# host.net
KiCad netlist of a schematic drawn in EAGLE
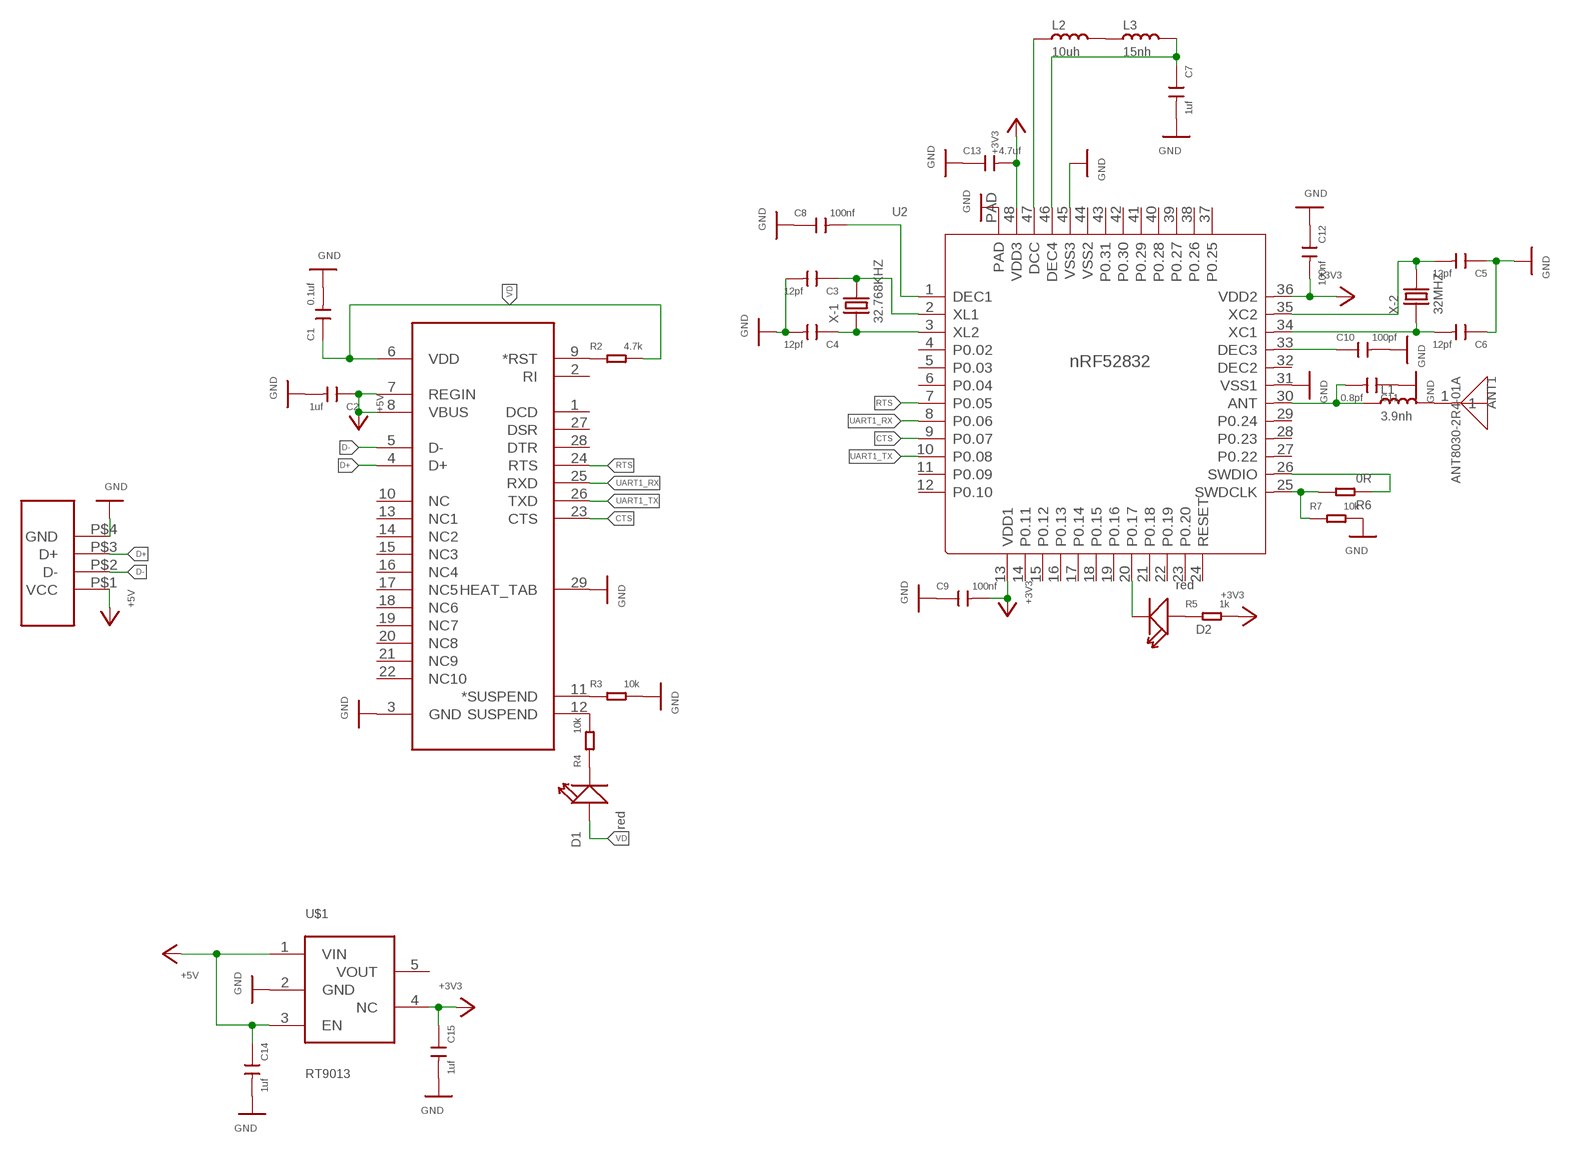
[diagram p0: schematic, sheet 1]

(export (version "E")
  (design (tool "Eeschema 10.0.6"))
  (components
    (comp (ref "ANT1")
      (value "ANT8030-2R4-01A")
      (footprint "eagle-import:ANTENNA")
      (libsource (lib "eagle-import") (part "ANTENNA"))
    )
    (comp (ref "C1")
      (value "0.1uf")
      (footprint "eagle-import:C0402")
      (fields (field (name "MPN") "CC0402BRNPO9BNR50"))
      (libsource (lib "eagle-import") (part "C(0402)"))
    )
    (comp (ref "C2")
      (value "1uf")
      (footprint "eagle-import:C0402")
      (fields (field (name "MPN") "CC0402BRNPO9BNR50"))
      (libsource (lib "eagle-import") (part "C(0402)"))
    )
    (comp (ref "C3")
      (value "12pf")
      (footprint "eagle-import:C0402")
      (fields (field (name "MPN") "CC0402BRNPO9BNR50"))
      (libsource (lib "eagle-import") (part "C(0402)"))
    )
    (comp (ref "C4")
      (value "12pf")
      (footprint "eagle-import:C0402")
      (fields (field (name "MPN") "CC0402BRNPO9BNR50"))
      (libsource (lib "eagle-import") (part "C(0402)"))
    )
    (comp (ref "C5")
      (value "12pf")
      (footprint "eagle-import:C0402")
      (fields (field (name "MPN") "CC0402BRNPO9BNR50"))
      (libsource (lib "eagle-import") (part "C(0402)"))
    )
    (comp (ref "C6")
      (value "12pf")
      (footprint "eagle-import:C0402")
      (fields (field (name "MPN") "CC0402BRNPO9BNR50"))
      (libsource (lib "eagle-import") (part "C(0402)"))
    )
    (comp (ref "C7")
      (value "1uf")
      (footprint "eagle-import:C0402")
      (fields (field (name "MPN") "CC0402BRNPO9BNR50"))
      (libsource (lib "eagle-import") (part "C(0402)"))
    )
    (comp (ref "C8")
      (value "100nf")
      (footprint "eagle-import:C0402")
      (fields (field (name "MPN") "CC0402BRNPO9BNR50"))
      (libsource (lib "eagle-import") (part "C(0402)"))
    )
    (comp (ref "C9")
      (value "100nf")
      (footprint "eagle-import:C0402")
      (fields (field (name "MPN") "CC0402BRNPO9BNR50"))
      (libsource (lib "eagle-import") (part "C(0402)"))
    )
    (comp (ref "C10")
      (value "100pf")
      (footprint "eagle-import:C0402")
      (fields (field (name "MPN") "CC0402BRNPO9BNR50"))
      (libsource (lib "eagle-import") (part "C(0402)"))
    )
    (comp (ref "C11")
      (value "0.8pf")
      (footprint "eagle-import:C0402")
      (fields (field (name "MPN") "CC0402BRNPO9BNR50"))
      (libsource (lib "eagle-import") (part "C(0402)"))
    )
    (comp (ref "C12")
      (value "100nf")
      (footprint "eagle-import:C0402")
      (fields (field (name "MPN") "CC0402BRNPO9BNR50"))
      (libsource (lib "eagle-import") (part "C(0402)"))
    )
    (comp (ref "C13")
      (value "4.7uf")
      (footprint "eagle-import:C0402")
      (fields (field (name "MPN") "CC0402BRNPO9BNR50"))
      (libsource (lib "eagle-import") (part "C(0402)"))
    )
    (comp (ref "C14")
      (value "1uf")
      (footprint "eagle-import:C0402")
      (fields (field (name "MPN") "CC0402BRNPO9BNR50"))
      (libsource (lib "eagle-import") (part "C(0402)"))
    )
    (comp (ref "C15")
      (value "1uf")
      (footprint "eagle-import:C0402")
      (fields (field (name "MPN") "CC0402BRNPO9BNR50"))
      (libsource (lib "eagle-import") (part "C(0402)"))
    )
    (comp (ref "CP1")
      (value "CP2102")
      (footprint "eagle-import:QFN28G_0.5-5X5MM")
      (libsource (lib "eagle-import") (part "CP2102"))
    )
    (comp (ref "D1")
      (value "red")
      (footprint "eagle-import:LED-0402")
      (fields (field (name "MPN") "BL-HB337A-AV-TRB"))
      (libsource (lib "eagle-import") (part "LED-(0402)"))
    )
    (comp (ref "D2")
      (value "red")
      (footprint "eagle-import:LED-0402")
      (fields (field (name "MPN") "BL-HB337A-AV-TRB"))
      (libsource (lib "eagle-import") (part "LED-(0402)"))
    )
    (comp (ref "L1")
      (value "3.9nh")
      (footprint "eagle-import:L0402")
      (libsource (lib "eagle-import") (part "INDUCTOR(0402)"))
    )
    (comp (ref "L2")
      (value "10uh")
      (footprint "eagle-import:L0402")
      (libsource (lib "eagle-import") (part "INDUCTOR(0402)"))
    )
    (comp (ref "L3")
      (value "15nh")
      (footprint "eagle-import:L0402")
      (libsource (lib "eagle-import") (part "INDUCTOR(0402)"))
    )
    (comp (ref "R2")
      (value "4.7k")
      (footprint "eagle-import:R0402")
      (fields (field (name "MPN") "RC0402JR-070RL"))
      (libsource (lib "eagle-import") (part "RES-(0402)"))
    )
    (comp (ref "R3")
      (value "10k")
      (footprint "eagle-import:R0402")
      (fields (field (name "MPN") "RC0402JR-070RL"))
      (libsource (lib "eagle-import") (part "RES-(0402)"))
    )
    (comp (ref "R4")
      (value "10k")
      (footprint "eagle-import:R0402")
      (fields (field (name "MPN") "RC0402JR-070RL"))
      (libsource (lib "eagle-import") (part "RES-(0402)"))
    )
    (comp (ref "R5")
      (value "1k")
      (footprint "eagle-import:R0402")
      (fields (field (name "MPN") "RC0402JR-070RL"))
      (libsource (lib "eagle-import") (part "RES-(0402)"))
    )
    (comp (ref "R6")
      (value "0R")
      (footprint "eagle-import:R0603")
      (fields (field (name "MPN") "RC0603FR-071M1L"))
      (libsource (lib "eagle-import") (part "RES-(0603)"))
    )
    (comp (ref "R7")
      (value "10k")
      (footprint "eagle-import:R0402")
      (fields (field (name "MPN") "RC0402JR-070RL"))
      (libsource (lib "eagle-import") (part "RES-(0402)"))
    )
    (comp (ref "U$1")
      (value "RT9013")
      (footprint "eagle-import:SC-70-5")
      (libsource (lib "eagle-import") (part "RT9013"))
    )
    (comp (ref "U1")
      (value "USB-4PIN")
      (footprint "eagle-import:USB-HW-4PIN")
      (libsource (lib "eagle-import") (part "USB-4PIN"))
    )
    (comp (ref "U2")
      (value "RF-51822")
      (footprint "eagle-import:QFN48G-0.4-6X6MM")
      (libsource (lib "eagle-import") (part "IC-NRF-52832(QFN48)"))
    )
    (comp (ref "X-1")
      (value "32.768KHZ")
      (footprint "eagle-import:32.768KHZ")
      (libsource (lib "eagle-import") (part "32.768KHZ"))
    )
    (comp (ref "X-2")
      (value "32MHZ")
      (footprint "eagle-import:16MHZ")
      (libsource (lib "eagle-import") (part "16MHZ"))
    )
  )
  (nets
    (net (code "1") (name "+3V3") (class "Default")
      (node (ref "C12") (pin "2") (pinfunction "2_2") (pintype "passive"))
      (node (ref "C13") (pin "2") (pinfunction "2_2") (pintype "passive"))
      (node (ref "C15") (pin "1") (pinfunction "1_1") (pintype "passive"))
      (node (ref "C9") (pin "2") (pinfunction "2_2") (pintype "passive"))
      (node (ref "R5") (pin "2") (pinfunction "2_2") (pintype "passive"))
      (node (ref "U$1") (pin "4") (pinfunction "NC_4") (pintype "bidirectional"))
      (node (ref "U2") (pin "13") (pinfunction "VDD1_13") (pintype "bidirectional"))
      (node (ref "U2") (pin "36") (pinfunction "VDD2_36") (pintype "bidirectional"))
      (node (ref "U2") (pin "48") (pinfunction "VDD3_48") (pintype "bidirectional"))
    )
    (net (code "2") (name "+5V") (class "Default")
      (node (ref "C14") (pin "1") (pinfunction "1_1") (pintype "passive"))
      (node (ref "C2") (pin "1") (pinfunction "1_1") (pintype "passive"))
      (node (ref "CP1") (pin "7") (pinfunction "REGIN_7") (pintype "bidirectional"))
      (node (ref "CP1") (pin "8") (pinfunction "VBUS_8") (pintype "bidirectional"))
      (node (ref "U$1") (pin "1") (pinfunction "VIN_1") (pintype "bidirectional"))
      (node (ref "U$1") (pin "3") (pinfunction "EN_3") (pintype "bidirectional"))
      (node (ref "U1") (pin "P$1") (pinfunction "VCC_P$1") (pintype "bidirectional"))
    )
    (net (code "3") (name "CTS") (class "Default")
      (node (ref "CP1") (pin "23") (pinfunction "CTS_23") (pintype "bidirectional"))
      (node (ref "U2") (pin "9") (pinfunction "P0.07_9") (pintype "bidirectional"))
    )
    (net (code "4") (name "D+") (class "Default")
      (node (ref "CP1") (pin "4") (pinfunction "D+_4") (pintype "bidirectional"))
      (node (ref "U1") (pin "P$3") (pinfunction "D+_P$3") (pintype "bidirectional"))
    )
    (net (code "5") (name "D-") (class "Default")
      (node (ref "CP1") (pin "5") (pinfunction "D-_5") (pintype "bidirectional"))
      (node (ref "U1") (pin "P$2") (pinfunction "D-_P$2") (pintype "bidirectional"))
    )
    (net (code "6") (name "GND") (class "Default")
      (node (ref "C1") (pin "2") (pinfunction "2_2") (pintype "passive"))
      (node (ref "C10") (pin "2") (pinfunction "2_2") (pintype "passive"))
      (node (ref "C11") (pin "1") (pinfunction "1_1") (pintype "passive"))
      (node (ref "C12") (pin "1") (pinfunction "1_1") (pintype "passive"))
      (node (ref "C13") (pin "1") (pinfunction "1_1") (pintype "passive"))
      (node (ref "C14") (pin "2") (pinfunction "2_2") (pintype "passive"))
      (node (ref "C15") (pin "2") (pinfunction "2_2") (pintype "passive"))
      (node (ref "C2") (pin "2") (pinfunction "2_2") (pintype "passive"))
      (node (ref "C3") (pin "2") (pinfunction "2_2") (pintype "passive"))
      (node (ref "C4") (pin "2") (pinfunction "2_2") (pintype "passive"))
      (node (ref "C5") (pin "1") (pinfunction "1_1") (pintype "passive"))
      (node (ref "C6") (pin "1") (pinfunction "1_1") (pintype "passive"))
      (node (ref "C7") (pin "2") (pinfunction "2_2") (pintype "passive"))
      (node (ref "C8") (pin "1") (pinfunction "1_1") (pintype "passive"))
      (node (ref "C9") (pin "1") (pinfunction "1_1") (pintype "passive"))
      (node (ref "CP1") (pin "29") (pinfunction "HEAT_TAB_29") (pintype "bidirectional"))
      (node (ref "CP1") (pin "3") (pinfunction "GND_3") (pintype "bidirectional"))
      (node (ref "R3") (pin "2") (pinfunction "2_2") (pintype "passive"))
      (node (ref "R7") (pin "2") (pinfunction "2_2") (pintype "passive"))
      (node (ref "U$1") (pin "2") (pinfunction "GND_2") (pintype "bidirectional"))
      (node (ref "U1") (pin "P$4") (pinfunction "GND_P$4") (pintype "bidirectional"))
      (node (ref "U2") (pin "31") (pinfunction "VSS1_31") (pintype "bidirectional"))
      (node (ref "U2") (pin "45") (pinfunction "VSS3_45") (pintype "bidirectional"))
      (node (ref "U2") (pin "PAD") (pinfunction "PAD_PAD") (pintype "bidirectional"))
    )
    (net (code "7") (name "Net-(ANT1-Pad1)") (class "Default")
      (node (ref "ANT1") (pin "1") (pinfunction "1_1") (pintype "bidirectional"))
      (node (ref "L1") (pin "2") (pinfunction "2_2") (pintype "passive"))
    )
    (net (code "8") (name "Net-(CP1-*RST)") (class "Default")
      (node (ref "CP1") (pin "9") (pinfunction "*RST_9") (pintype "bidirectional"))
      (node (ref "R2") (pin "1") (pinfunction "1_1") (pintype "passive"))
    )
    (net (code "9") (name "Net-(CP1-*SUSPEND)") (class "Default")
      (node (ref "CP1") (pin "11") (pinfunction "*SUSPEND_11") (pintype "bidirectional"))
      (node (ref "R3") (pin "1") (pinfunction "1_1") (pintype "passive"))
    )
    (net (code "10") (name "Net-(CP1-SUSPEND)") (class "Default")
      (node (ref "CP1") (pin "12") (pinfunction "SUSPEND_12") (pintype "bidirectional"))
      (node (ref "R4") (pin "2") (pinfunction "2_2") (pintype "passive"))
    )
    (net (code "11") (name "Net-(D1-Pad-)") (class "Default")
      (node (ref "D1") (pin "-") (pinfunction "-_-") (pintype "passive"))
      (node (ref "R4") (pin "1") (pinfunction "1_1") (pintype "passive"))
    )
    (net (code "12") (name "Net-(D2-Pad+)") (class "Default")
      (node (ref "D2") (pin "+") (pinfunction "+_+") (pintype "passive"))
      (node (ref "R5") (pin "1") (pinfunction "1_1") (pintype "passive"))
    )
    (net (code "13") (name "Net-(L2-Pad2)") (class "Default")
      (node (ref "L2") (pin "2") (pinfunction "2_2") (pintype "passive"))
      (node (ref "L3") (pin "1") (pinfunction "1_1") (pintype "passive"))
    )
    (net (code "14") (name "Net-(U2-ANT)") (class "Default")
      (node (ref "C11") (pin "2") (pinfunction "2_2") (pintype "passive"))
      (node (ref "L1") (pin "1") (pinfunction "1_1") (pintype "passive"))
      (node (ref "U2") (pin "30") (pinfunction "ANT_30") (pintype "bidirectional"))
    )
    (net (code "15") (name "Net-(U2-DCC)") (class "Default")
      (node (ref "L2") (pin "1") (pinfunction "1_1") (pintype "passive"))
      (node (ref "U2") (pin "47") (pinfunction "DCC_47") (pintype "bidirectional"))
    )
    (net (code "16") (name "Net-(U2-DEC1)") (class "Default")
      (node (ref "C8") (pin "2") (pinfunction "2_2") (pintype "passive"))
      (node (ref "U2") (pin "1") (pinfunction "DEC1_1") (pintype "bidirectional"))
    )
    (net (code "17") (name "Net-(U2-DEC3)") (class "Default")
      (node (ref "C10") (pin "1") (pinfunction "1_1") (pintype "passive"))
      (node (ref "U2") (pin "33") (pinfunction "DEC3_33") (pintype "bidirectional"))
    )
    (net (code "18") (name "Net-(U2-DEC4)") (class "Default")
      (node (ref "C7") (pin "1") (pinfunction "1_1") (pintype "passive"))
      (node (ref "L3") (pin "2") (pinfunction "2_2") (pintype "passive"))
      (node (ref "U2") (pin "46") (pinfunction "DEC4_46") (pintype "bidirectional"))
    )
    (net (code "19") (name "Net-(U2-P0.17)") (class "Default")
      (node (ref "D2") (pin "-") (pinfunction "-_-") (pintype "passive"))
      (node (ref "U2") (pin "20") (pinfunction "P0.17_20") (pintype "bidirectional"))
    )
    (net (code "20") (name "Net-(U2-SWDCLK)") (class "Default")
      (node (ref "R6") (pin "2") (pinfunction "2_2") (pintype "passive"))
      (node (ref "R7") (pin "1") (pinfunction "1_1") (pintype "passive"))
      (node (ref "U2") (pin "25") (pinfunction "SWDCLK_25") (pintype "bidirectional"))
    )
    (net (code "21") (name "Net-(U2-SWDIO)") (class "Default")
      (node (ref "R6") (pin "1") (pinfunction "1_1") (pintype "passive"))
      (node (ref "U2") (pin "26") (pinfunction "SWDIO_26") (pintype "bidirectional"))
    )
    (net (code "22") (name "Net-(U2-XC1)") (class "Default")
      (node (ref "C6") (pin "2") (pinfunction "2_2") (pintype "passive"))
      (node (ref "U2") (pin "34") (pinfunction "XC1_34") (pintype "bidirectional"))
      (node (ref "X-2") (pin "1") (pinfunction "1_1") (pintype "passive"))
    )
    (net (code "23") (name "Net-(U2-XC2)") (class "Default")
      (node (ref "C5") (pin "2") (pinfunction "2_2") (pintype "passive"))
      (node (ref "U2") (pin "35") (pinfunction "XC2_35") (pintype "bidirectional"))
      (node (ref "X-2") (pin "3") (pinfunction "2_3") (pintype "passive"))
    )
    (net (code "24") (name "Net-(U2-XL1)") (class "Default")
      (node (ref "C3") (pin "1") (pinfunction "1_1") (pintype "passive"))
      (node (ref "U2") (pin "2") (pinfunction "XL1_2") (pintype "bidirectional"))
      (node (ref "X-1") (pin "P$2") (pinfunction "2_P$2") (pintype "passive"))
    )
    (net (code "25") (name "Net-(U2-XL2)") (class "Default")
      (node (ref "C4") (pin "1") (pinfunction "1_1") (pintype "passive"))
      (node (ref "U2") (pin "3") (pinfunction "XL2_3") (pintype "bidirectional"))
      (node (ref "X-1") (pin "P$1") (pinfunction "1_P$1") (pintype "passive"))
    )
    (net (code "26") (name "RTS") (class "Default")
      (node (ref "CP1") (pin "24") (pinfunction "RTS_24") (pintype "bidirectional"))
      (node (ref "U2") (pin "7") (pinfunction "P0.05_7") (pintype "bidirectional"))
    )
    (net (code "27") (name "UART1_RX") (class "Default")
      (node (ref "CP1") (pin "25") (pinfunction "RXD_25") (pintype "bidirectional"))
      (node (ref "U2") (pin "8") (pinfunction "P0.06_8") (pintype "bidirectional"))
    )
    (net (code "28") (name "UART1_TX") (class "Default")
      (node (ref "CP1") (pin "26") (pinfunction "TXD_26") (pintype "bidirectional"))
      (node (ref "U2") (pin "10") (pinfunction "P0.08_10") (pintype "bidirectional"))
    )
    (net (code "29") (name "VD") (class "Default")
      (node (ref "C1") (pin "1") (pinfunction "1_1") (pintype "passive"))
      (node (ref "CP1") (pin "6") (pinfunction "VDD_6") (pintype "bidirectional"))
      (node (ref "D1") (pin "+") (pinfunction "+_+") (pintype "passive"))
      (node (ref "R2") (pin "2") (pinfunction "2_2") (pintype "passive"))
    )
    (net (code "30") (name "unconnected-(CP1-DCD-Pad1)") (class "Default")
      (node (ref "CP1") (pin "1") (pinfunction "DCD_1") (pintype "bidirectional"))
    )
    (net (code "31") (name "unconnected-(CP1-DSR-Pad27)") (class "Default")
      (node (ref "CP1") (pin "27") (pinfunction "DSR_27") (pintype "bidirectional"))
    )
    (net (code "32") (name "unconnected-(CP1-DTR-Pad28)") (class "Default")
      (node (ref "CP1") (pin "28") (pinfunction "DTR_28") (pintype "bidirectional"))
    )
    (net (code "33") (name "unconnected-(CP1-NC-Pad10)") (class "Default")
      (node (ref "CP1") (pin "10") (pinfunction "NC_10") (pintype "bidirectional"))
    )
    (net (code "34") (name "unconnected-(CP1-NC1-Pad13)") (class "Default")
      (node (ref "CP1") (pin "13") (pinfunction "NC1_13") (pintype "bidirectional"))
    )
    (net (code "35") (name "unconnected-(CP1-NC2-Pad14)") (class "Default")
      (node (ref "CP1") (pin "14") (pinfunction "NC2_14") (pintype "bidirectional"))
    )
    (net (code "36") (name "unconnected-(CP1-NC3-Pad15)") (class "Default")
      (node (ref "CP1") (pin "15") (pinfunction "NC3_15") (pintype "bidirectional"))
    )
    (net (code "37") (name "unconnected-(CP1-NC4-Pad16)") (class "Default")
      (node (ref "CP1") (pin "16") (pinfunction "NC4_16") (pintype "bidirectional"))
    )
    (net (code "38") (name "unconnected-(CP1-NC5-Pad17)") (class "Default")
      (node (ref "CP1") (pin "17") (pinfunction "NC5_17") (pintype "bidirectional"))
    )
    (net (code "39") (name "unconnected-(CP1-NC6-Pad18)") (class "Default")
      (node (ref "CP1") (pin "18") (pinfunction "NC6_18") (pintype "bidirectional"))
    )
    (net (code "40") (name "unconnected-(CP1-NC7-Pad19)") (class "Default")
      (node (ref "CP1") (pin "19") (pinfunction "NC7_19") (pintype "bidirectional"))
    )
    (net (code "41") (name "unconnected-(CP1-NC8-Pad20)") (class "Default")
      (node (ref "CP1") (pin "20") (pinfunction "NC8_20") (pintype "bidirectional"))
    )
    (net (code "42") (name "unconnected-(CP1-NC9-Pad21)") (class "Default")
      (node (ref "CP1") (pin "21") (pinfunction "NC9_21") (pintype "bidirectional"))
    )
    (net (code "43") (name "unconnected-(CP1-NC10-Pad22)") (class "Default")
      (node (ref "CP1") (pin "22") (pinfunction "NC10_22") (pintype "bidirectional"))
    )
    (net (code "44") (name "unconnected-(CP1-RI-Pad2)") (class "Default")
      (node (ref "CP1") (pin "2") (pinfunction "RI_2") (pintype "bidirectional"))
    )
    (net (code "45") (name "unconnected-(U$1-VOUT-Pad5)") (class "Default")
      (node (ref "U$1") (pin "5") (pinfunction "VOUT_5") (pintype "bidirectional"))
    )
    (net (code "46") (name "unconnected-(U2-DEC2-Pad32)") (class "Default")
      (node (ref "U2") (pin "32") (pinfunction "DEC2_32") (pintype "bidirectional"))
    )
    (net (code "47") (name "unconnected-(U2-P0.02-Pad4)") (class "Default")
      (node (ref "U2") (pin "4") (pinfunction "P0.02_4") (pintype "bidirectional"))
    )
    (net (code "48") (name "unconnected-(U2-P0.03-Pad5)") (class "Default")
      (node (ref "U2") (pin "5") (pinfunction "P0.03_5") (pintype "bidirectional"))
    )
    (net (code "49") (name "unconnected-(U2-P0.04-Pad6)") (class "Default")
      (node (ref "U2") (pin "6") (pinfunction "P0.04_6") (pintype "bidirectional"))
    )
    (net (code "50") (name "unconnected-(U2-P0.09-Pad11)") (class "Default")
      (node (ref "U2") (pin "11") (pinfunction "P0.09_11") (pintype "bidirectional"))
    )
    (net (code "51") (name "unconnected-(U2-P0.10-Pad12)") (class "Default")
      (node (ref "U2") (pin "12") (pinfunction "P0.10_12") (pintype "bidirectional"))
    )
    (net (code "52") (name "unconnected-(U2-P0.11-Pad14)") (class "Default")
      (node (ref "U2") (pin "14") (pinfunction "P0.11_14") (pintype "bidirectional"))
    )
    (net (code "53") (name "unconnected-(U2-P0.12-Pad15)") (class "Default")
      (node (ref "U2") (pin "15") (pinfunction "P0.12_15") (pintype "bidirectional"))
    )
    (net (code "54") (name "unconnected-(U2-P0.13-Pad16)") (class "Default")
      (node (ref "U2") (pin "16") (pinfunction "P0.13_16") (pintype "bidirectional"))
    )
    (net (code "55") (name "unconnected-(U2-P0.14-Pad17)") (class "Default")
      (node (ref "U2") (pin "17") (pinfunction "P0.14_17") (pintype "bidirectional"))
    )
    (net (code "56") (name "unconnected-(U2-P0.15-Pad18)") (class "Default")
      (node (ref "U2") (pin "18") (pinfunction "P0.15_18") (pintype "bidirectional"))
    )
    (net (code "57") (name "unconnected-(U2-P0.16-Pad19)") (class "Default")
      (node (ref "U2") (pin "19") (pinfunction "P0.16_19") (pintype "bidirectional"))
    )
    (net (code "58") (name "unconnected-(U2-P0.18-Pad21)") (class "Default")
      (node (ref "U2") (pin "21") (pinfunction "P0.18_21") (pintype "bidirectional"))
    )
    (net (code "59") (name "unconnected-(U2-P0.19-Pad22)") (class "Default")
      (node (ref "U2") (pin "22") (pinfunction "P0.19_22") (pintype "bidirectional"))
    )
    (net (code "60") (name "unconnected-(U2-P0.20-Pad23)") (class "Default")
      (node (ref "U2") (pin "23") (pinfunction "P0.20_23") (pintype "bidirectional"))
    )
    (net (code "61") (name "unconnected-(U2-P0.22-Pad27)") (class "Default")
      (node (ref "U2") (pin "27") (pinfunction "P0.22_27") (pintype "bidirectional"))
    )
    (net (code "62") (name "unconnected-(U2-P0.23-Pad28)") (class "Default")
      (node (ref "U2") (pin "28") (pinfunction "P0.23_28") (pintype "bidirectional"))
    )
    (net (code "63") (name "unconnected-(U2-P0.24-Pad29)") (class "Default")
      (node (ref "U2") (pin "29") (pinfunction "P0.24_29") (pintype "bidirectional"))
    )
    (net (code "64") (name "unconnected-(U2-P0.25-Pad37)") (class "Default")
      (node (ref "U2") (pin "37") (pinfunction "P0.25_37") (pintype "bidirectional"))
    )
    (net (code "65") (name "unconnected-(U2-P0.26-Pad38)") (class "Default")
      (node (ref "U2") (pin "38") (pinfunction "P0.26_38") (pintype "bidirectional"))
    )
    (net (code "66") (name "unconnected-(U2-P0.27-Pad39)") (class "Default")
      (node (ref "U2") (pin "39") (pinfunction "P0.27_39") (pintype "bidirectional"))
    )
    (net (code "67") (name "unconnected-(U2-P0.28-Pad40)") (class "Default")
      (node (ref "U2") (pin "40") (pinfunction "P0.28_40") (pintype "bidirectional"))
    )
    (net (code "68") (name "unconnected-(U2-P0.29-Pad41)") (class "Default")
      (node (ref "U2") (pin "41") (pinfunction "P0.29_41") (pintype "bidirectional"))
    )
    (net (code "69") (name "unconnected-(U2-P0.30-Pad42)") (class "Default")
      (node (ref "U2") (pin "42") (pinfunction "P0.30_42") (pintype "bidirectional"))
    )
    (net (code "70") (name "unconnected-(U2-P0.31-Pad43)") (class "Default")
      (node (ref "U2") (pin "43") (pinfunction "P0.31_43") (pintype "bidirectional"))
    )
    (net (code "71") (name "unconnected-(U2-RESET-Pad24)") (class "Default")
      (node (ref "U2") (pin "24") (pinfunction "RESET_24") (pintype "bidirectional"))
    )
    (net (code "72") (name "unconnected-(U2-VSS2-Pad44)") (class "Default")
      (node (ref "U2") (pin "44") (pinfunction "VSS2_44") (pintype "bidirectional"))
    )
  )
)
